# USB_Distribution.net
KiCad netlist of a schematic drawn in Altium Designer
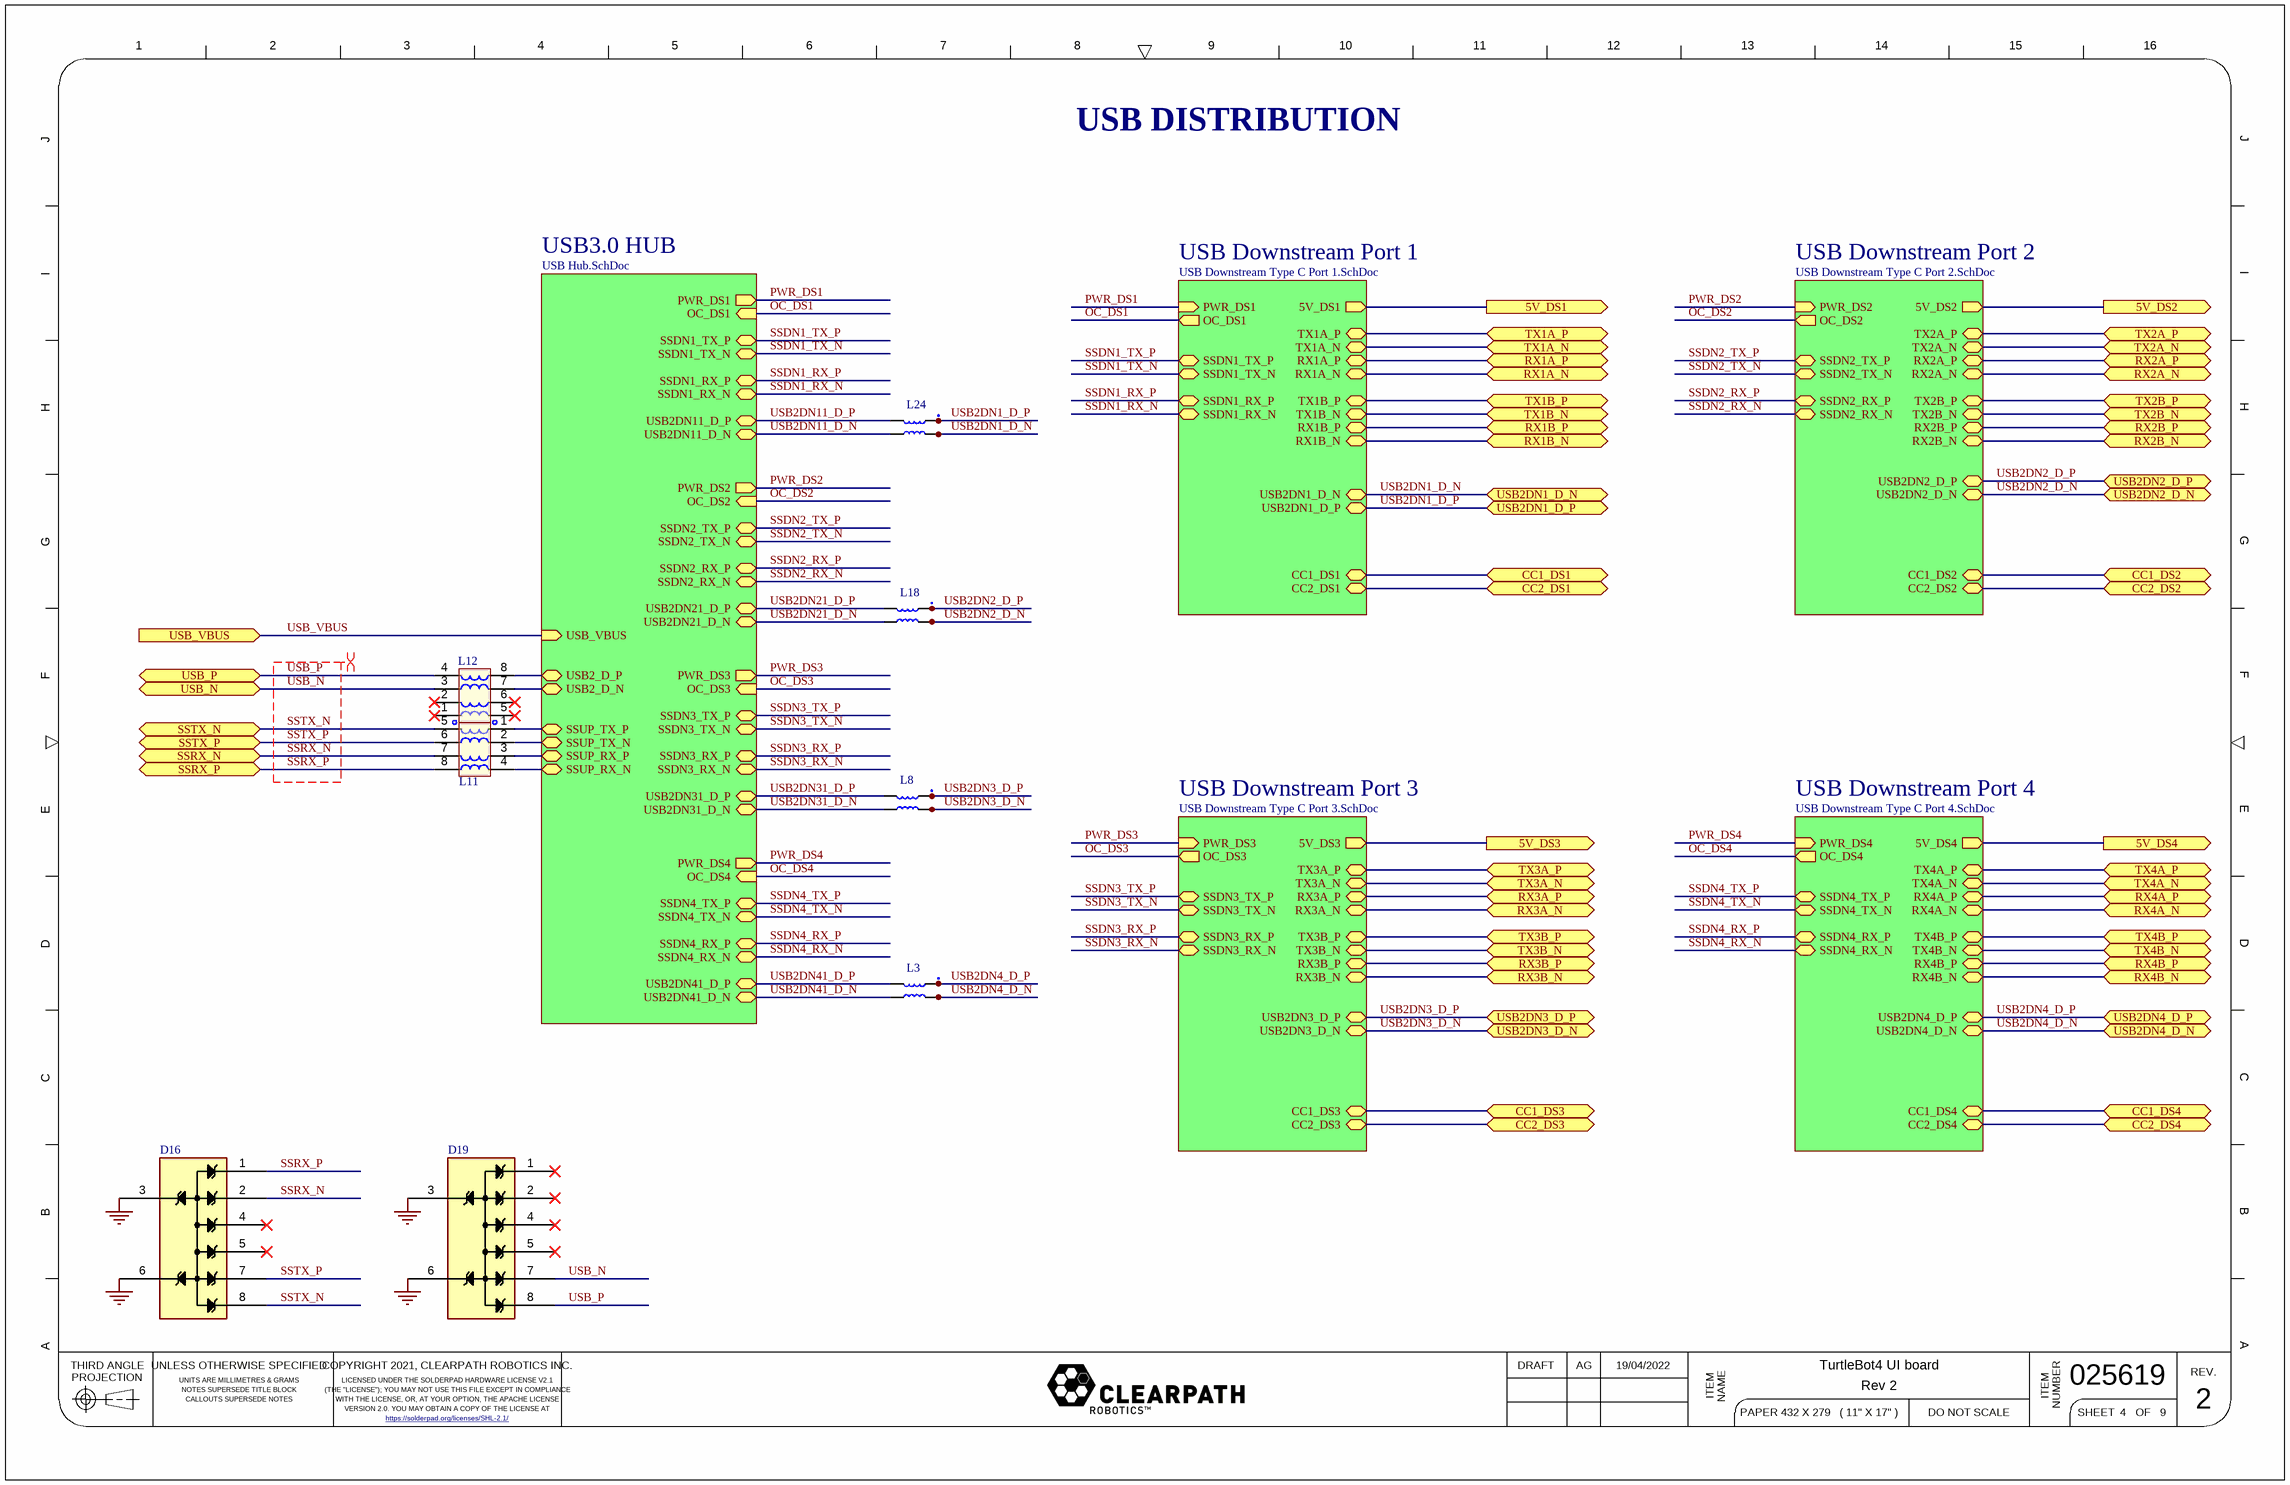
[diagram p0: USB Distribution.SchDoc]

(export (version "E")
  (design (tool "Eeschema 10.0.6"))
  (components
    (comp (ref "D16")
      (value "ESD7016")
      (footprint "ESD7016")
      (description "USB3 TVS diode assy")
      (fields (field (name "MFG") "ON Semi"))
      (libsource (lib "ONSemi_ESD7016") (part "ESD7016"))
    )
    (comp (ref "D19")
      (value "ESD7016")
      (footprint "ESD7016")
      (description "USB3 TVS diode assy")
      (fields (field (name "MFG") "ON Semi"))
      (libsource (lib "ONSemi_ESD7016") (part "ESD7016"))
    )
    (comp (ref "L3")
      (value "CMC 100MA 2LN 90 OHM SMD2")
      (footprint "MCZ1210CH900L2:MCZ1210CH900L2")
      (description "Line Common Mode Choke Surface Mount 90 Ohms 100mA DCR 5Ohm")
      (libsource (lib "cmc_90_ohms") (part "CMC 90_Ohms"))
    )
    (comp (ref "L8")
      (value "CMC 100MA 2LN 90 OHM SMD2")
      (footprint "MCZ1210CH900L2:MCZ1210CH900L2")
      (description "Line Common Mode Choke Surface Mount 90 Ohms 100mA DCR 5Ohm")
      (libsource (lib "cmc_90_ohms") (part "CMC 90_Ohms"))
    )
    (comp (ref "L11")
      (value "CMC 120MA 4LN 90 OHM SMD")
      (footprint "DLP2ADA900HL4L(8-pin):FIL_DLP2ADA900HL4L")
      (description "Chip Common Mode Choke Coil Arrays")
      (fields (field (name "MP") "DLP2ADA900HL4L"))
      (libsource (lib "DLP2ADA900HL4L") (part "DLP2ADA900HL4L"))
    )
    (comp (ref "L12")
      (value "CMC 120MA 4LN 90 OHM SMD")
      (footprint "DLP2ADA900HL4L(8-pin):FIL_DLP2ADA900HL4L")
      (description "Chip Common Mode Choke Coil Arrays")
      (fields (field (name "MP") "DLP2ADA900HL4L"))
      (libsource (lib "") (part "DLP2ADA900HL4L_1"))
    )
    (comp (ref "L18")
      (value "CMC 100MA 2LN 90 OHM SMD2")
      (footprint "MCZ1210CH900L2:MCZ1210CH900L2")
      (description "Line Common Mode Choke Surface Mount 90 Ohms 100mA DCR 5Ohm")
      (libsource (lib "cmc_90_ohms") (part "CMC 90_Ohms"))
    )
    (comp (ref "L24")
      (value "CMC 100MA 2LN 90 OHM SMD2")
      (footprint "MCZ1210CH900L2:MCZ1210CH900L2")
      (description "Line Common Mode Choke Surface Mount 90 Ohms 100mA DCR 5Ohm")
      (libsource (lib "cmc_90_ohms") (part "CMC 90_Ohms"))
    )
  )
  (nets
    (net (code "53") (name "/SSRX_N") (class "Default")
      (node (ref "D16") (pin "2") (pintype "passive"))
      (node (ref "L11") (pin "7") (pinfunction "7_7") (pintype "passive"))
    )
    (net (code "54") (name "/SSRX_P") (class "Default")
      (node (ref "D16") (pin "1") (pinfunction "1_1") (pintype "passive"))
      (node (ref "L11") (pin "8") (pinfunction "8_8") (pintype "passive"))
    )
    (net (code "55") (name "/SSTX_N") (class "Default")
      (node (ref "D16") (pin "8") (pintype "passive"))
      (node (ref "L11") (pin "5") (pinfunction "5_5") (pintype "passive"))
    )
    (net (code "56") (name "/SSTX_P") (class "Default")
      (node (ref "D16") (pin "7") (pintype "passive"))
      (node (ref "L11") (pin "6") (pinfunction "6_6") (pintype "passive"))
    )
    (net (code "57") (name "/SSUP_RX_N") (class "Default")
      (node (ref "L11") (pin "4") (pinfunction "4_4") (pintype "passive"))
    )
    (net (code "58") (name "/SSUP_RX_P") (class "Default")
      (node (ref "L11") (pin "3") (pinfunction "3_3") (pintype "passive"))
    )
    (net (code "59") (name "/SSUP_TX_N") (class "Default")
      (node (ref "L11") (pin "2") (pinfunction "2_2") (pintype "passive"))
    )
    (net (code "60") (name "/SSUP_TX_P") (class "Default")
      (node (ref "L11") (pin "1") (pinfunction "1_1") (pintype "passive"))
    )
    (net (code "77") (name "/USB2DN1_D_N") (class "Default")
      (node (ref "L24") (pin "2") (pinfunction "2_2") (pintype "passive"))
    )
    (net (code "78") (name "/USB2DN1_D_P") (class "Default")
      (node (ref "L24") (pin "1") (pinfunction "1_1") (pintype "passive"))
    )
    (net (code "79") (name "/USB2DN2_D_N") (class "Default")
      (node (ref "L18") (pin "2") (pinfunction "2_2") (pintype "passive"))
    )
    (net (code "80") (name "/USB2DN2_D_P") (class "Default")
      (node (ref "L18") (pin "1") (pinfunction "1_1") (pintype "passive"))
    )
    (net (code "81") (name "/USB2DN3_D_N") (class "Default")
      (node (ref "L8") (pin "2") (pinfunction "2_2") (pintype "passive"))
    )
    (net (code "82") (name "/USB2DN3_D_P") (class "Default")
      (node (ref "L8") (pin "1") (pinfunction "1_1") (pintype "passive"))
    )
    (net (code "83") (name "/USB2DN4_D_N") (class "Default")
      (node (ref "L3") (pin "2") (pinfunction "2_2") (pintype "passive"))
    )
    (net (code "84") (name "/USB2DN4_D_P") (class "Default")
      (node (ref "L3") (pin "1") (pinfunction "1_1") (pintype "passive"))
    )
    (net (code "85") (name "/USB2DN11_D_N") (class "Default")
      (node (ref "L24") (pin "3") (pinfunction "3_3") (pintype "passive"))
    )
    (net (code "86") (name "/USB2DN11_D_P") (class "Default")
      (node (ref "L24") (pin "4") (pinfunction "4_4") (pintype "passive"))
    )
    (net (code "87") (name "/USB2DN21_D_N") (class "Default")
      (node (ref "L18") (pin "3") (pinfunction "3_3") (pintype "passive"))
    )
    (net (code "88") (name "/USB2DN21_D_P") (class "Default")
      (node (ref "L18") (pin "4") (pinfunction "4_4") (pintype "passive"))
    )
    (net (code "89") (name "/USB2DN31_D_N") (class "Default")
      (node (ref "L8") (pin "3") (pinfunction "3_3") (pintype "passive"))
    )
    (net (code "90") (name "/USB2DN31_D_P") (class "Default")
      (node (ref "L8") (pin "4") (pinfunction "4_4") (pintype "passive"))
    )
    (net (code "91") (name "/USB2DN41_D_N") (class "Default")
      (node (ref "L3") (pin "3") (pinfunction "3_3") (pintype "passive"))
    )
    (net (code "92") (name "/USB2DN41_D_P") (class "Default")
      (node (ref "L3") (pin "4") (pinfunction "4_4") (pintype "passive"))
    )
    (net (code "93") (name "/USB2_D_N") (class "Default")
      (node (ref "L12") (pin "7") (pinfunction "7_7") (pintype "passive"))
    )
    (net (code "94") (name "/USB2_D_P") (class "Default")
      (node (ref "L12") (pin "8") (pinfunction "8_8") (pintype "passive"))
    )
    (net (code "95") (name "/USB_N") (class "Default")
      (node (ref "D19") (pin "7") (pintype "passive"))
      (node (ref "L12") (pin "3") (pinfunction "3_3") (pintype "passive"))
    )
    (net (code "96") (name "/USB_P") (class "Default")
      (node (ref "D19") (pin "8") (pintype "passive"))
      (node (ref "L12") (pin "4") (pinfunction "4_4") (pintype "passive"))
    )
    (net (code "98") (name "GND") (class "Default")
      (node (ref "D16") (pin "3") (pintype "passive"))
      (node (ref "D16") (pin "6") (pintype "passive"))
      (node (ref "D19") (pin "3") (pintype "passive"))
      (node (ref "D19") (pin "6") (pintype "passive"))
    )
    (net (code "99") (name "unconnected-(D16-Pad4)") (class "Default")
      (node (ref "D16") (pin "4") (pintype "passive+no_connect"))
    )
    (net (code "100") (name "unconnected-(D16-Pad5)") (class "Default")
      (node (ref "D16") (pin "5") (pintype "passive+no_connect"))
    )
    (net (code "101") (name "unconnected-(D19-Pad1)") (class "Default")
      (node (ref "D19") (pin "1") (pinfunction "1_1") (pintype "passive+no_connect"))
    )
    (net (code "102") (name "unconnected-(D19-Pad2)") (class "Default")
      (node (ref "D19") (pin "2") (pintype "passive+no_connect"))
    )
    (net (code "103") (name "unconnected-(D19-Pad4)") (class "Default")
      (node (ref "D19") (pin "4") (pintype "passive+no_connect"))
    )
    (net (code "104") (name "unconnected-(D19-Pad5)") (class "Default")
      (node (ref "D19") (pin "5") (pintype "passive+no_connect"))
    )
    (net (code "105") (name "unconnected-(L12-Pad1)") (class "Default")
      (node (ref "L12") (pin "1") (pinfunction "1_1") (pintype "passive+no_connect"))
    )
    (net (code "106") (name "unconnected-(L12-Pad2)") (class "Default")
      (node (ref "L12") (pin "2") (pinfunction "2_2") (pintype "passive+no_connect"))
    )
    (net (code "107") (name "unconnected-(L12-Pad5)") (class "Default")
      (node (ref "L12") (pin "5") (pinfunction "5_5") (pintype "passive+no_connect"))
    )
    (net (code "108") (name "unconnected-(L12-Pad6)") (class "Default")
      (node (ref "L12") (pin "6") (pinfunction "6_6") (pintype "passive+no_connect"))
    )
  )
)
